# CtrlBoxV2.net
KiCad netlist of a schematic drawn in Altium Designer
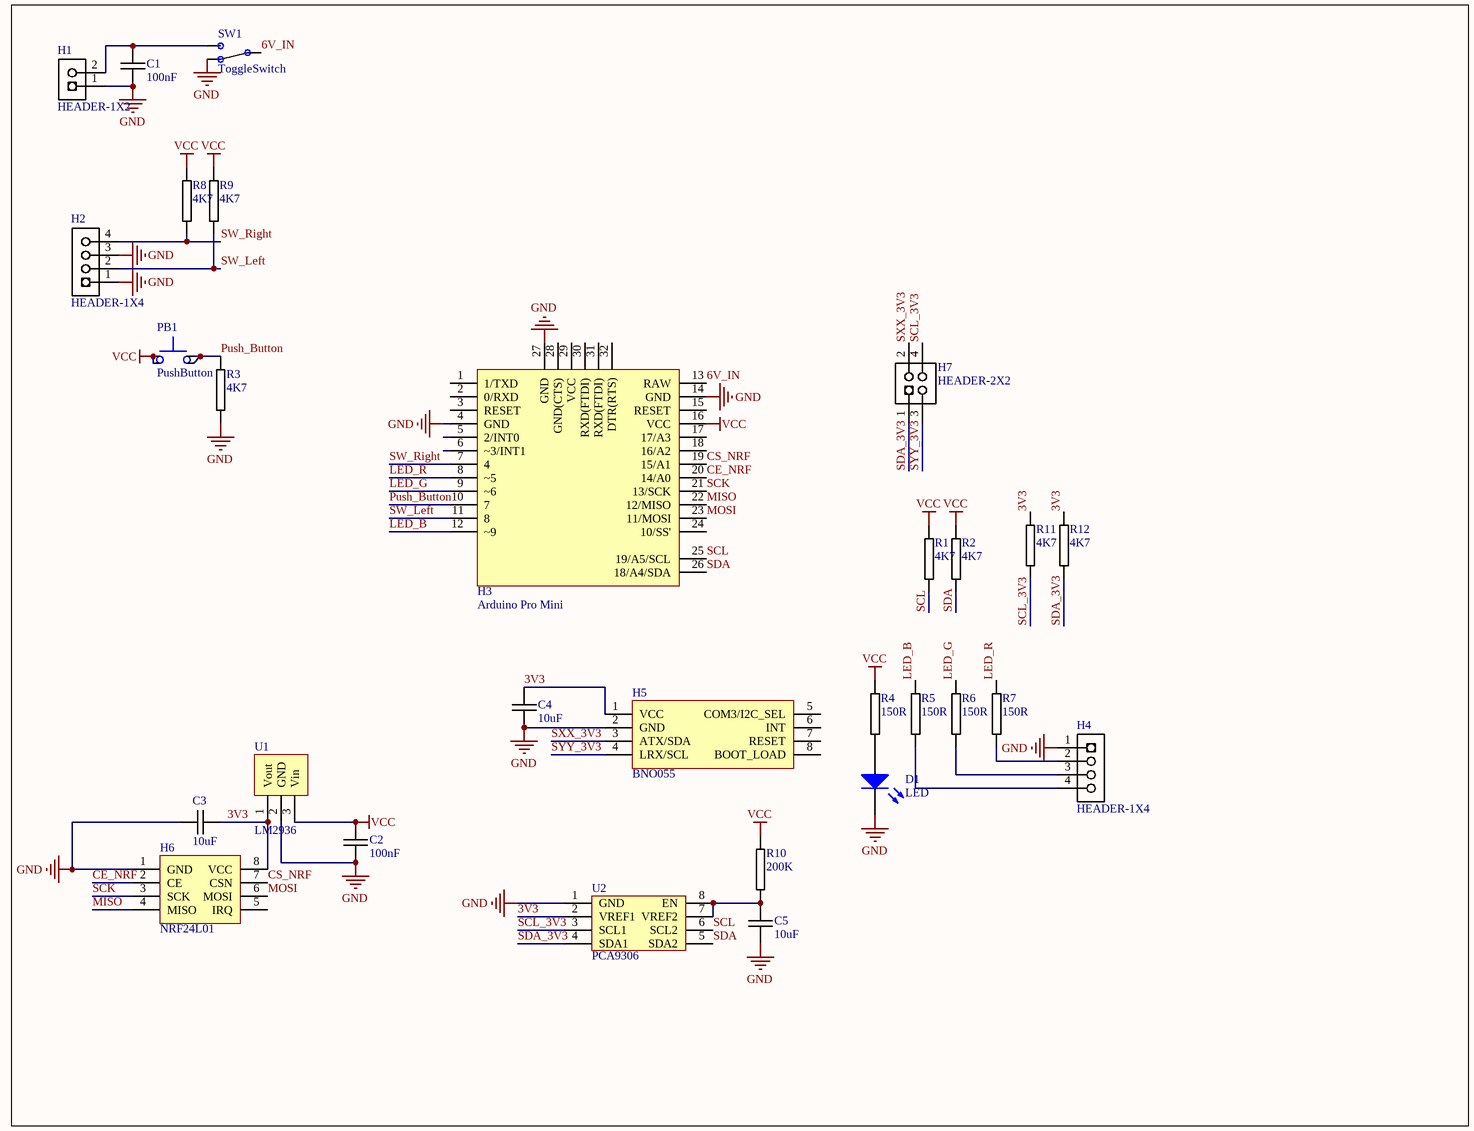
[diagram p0: CtrlBoxV2.SchDoc]

(export (version "E")
  (design (tool "Eeschema 10.0.6"))
  (components
    (comp (ref "C1")
      (value "100nF")
      (footprint "0805C-TBD")
      (description "CAPACITOR 0805 CERAMIC")
      (libsource (lib "vh_altium_library") (part "0805C-100nF-25V-X7R-MUR"))
    )
    (comp (ref "C2")
      (value "100nF")
      (footprint "0805C-TBD")
      (description "CAPACITOR 0805 CERAMIC")
      (libsource (lib "vh_altium_library") (part "0805C-100nF-25V-X7R-MUR"))
    )
    (comp (ref "C3")
      (value "10uF")
      (footprint "0805C-GENERIC")
      (description "CAPACITOR 0805 CERAMIC")
      (fields
        (field (name "MANUFACTURER PART NUMBER") "C2012X5R1C106M")
        (field (name "MANUFACTURER") "TDK Corporation")
      )
      (libsource (lib "vh_altium_library") (part "0805C-10UF-16V-X5R-TDK"))
    )
    (comp (ref "C4")
      (value "10uF")
      (footprint "0805C-GENERIC")
      (description "CAPACITOR 0805 CERAMIC")
      (fields
        (field (name "MANUFACTURER PART NUMBER") "C2012X5R1C106M")
        (field (name "MANUFACTURER") "TDK Corporation")
      )
      (libsource (lib "vh_altium_library") (part "0805C-10UF-16V-X5R-TDK"))
    )
    (comp (ref "C5")
      (value "10uF")
      (footprint "0805C-GENERIC")
      (description "CAPACITOR 0805 CERAMIC")
      (fields
        (field (name "MANUFACTURER PART NUMBER") "C2012X5R1C106M")
        (field (name "MANUFACTURER") "TDK Corporation")
      )
      (libsource (lib "vh_altium_library") (part "0805C-10UF-16V-X5R-TDK"))
    )
    (comp (ref "D1")
      (value "LED")
      (footprint "LED")
      (description "Small LED")
      (libsource (lib "Components") (part "LED"))
    )
    (comp (ref "H1")
      (value "HEADER-1X2")
      (footprint "HEADER-1X2")
      (libsource (lib "vh_altium_library") (part "HEADER-1X2"))
    )
    (comp (ref "H2")
      (value "HEADER-1X4")
      (footprint "HEADER-1X4")
      (libsource (lib "vh_altium_library") (part "HEADER-1X4"))
    )
    (comp (ref "H3")
      (value "Arduino Pro Mini")
      (footprint "Arduino Pro Mini")
      (libsource (lib "Components") (part "Arduino Pro Mini"))
    )
    (comp (ref "H4")
      (value "HEADER-1X4")
      (footprint "HEADER-1X4")
      (libsource (lib "vh_altium_library") (part "HEADER-1X4"))
    )
    (comp (ref "H5")
      (value "BNO055")
      (footprint "BNO055")
      (description "Accel+Gyro+Mag")
      (libsource (lib "Components") (part "BNO055"))
    )
    (comp (ref "H6")
      (value "NRF24L01")
      (footprint "NRF24L01")
      (description "Radio Transceiver")
      (libsource (lib "Components") (part "NRF24L01"))
    )
    (comp (ref "H7")
      (value "HEADER-2X2")
      (footprint "HEADER-2X2")
      (libsource (lib "vh_altium_library") (part "HEADER-2X2"))
    )
    (comp (ref "PB1")
      (value "PushButton")
      (footprint "PushButton")
      (libsource (lib "SBv1Components") (part "PushButton"))
    )
    (comp (ref "R1")
      (value "4K7")
      (footprint "0805R-4K7")
      (description "RESISTOR 0805 1/4 WATT THIN FILM")
      (libsource (lib "vh_altium_library") (part "0805R-4K7"))
    )
    (comp (ref "R2")
      (value "4K7")
      (footprint "0805R-4K7")
      (description "RESISTOR 0805 1/4 WATT THIN FILM")
      (libsource (lib "vh_altium_library") (part "0805R-4K7"))
    )
    (comp (ref "R3")
      (value "4K7")
      (footprint "0805R-4K7")
      (description "RESISTOR 0805 1/4 WATT THIN FILM")
      (libsource (lib "vh_altium_library") (part "0805R-4K7"))
    )
    (comp (ref "R4")
      (value "150R")
      (footprint "0805R-150")
      (description "RESISTOR 0805 1/4 WATT THIN FILM")
      (libsource (lib "vh_altium_library") (part "0805R-150"))
    )
    (comp (ref "R5")
      (value "150R")
      (footprint "0805R-150")
      (description "RESISTOR 0805 1/4 WATT THIN FILM")
      (libsource (lib "vh_altium_library") (part "0805R-150"))
    )
    (comp (ref "R6")
      (value "150R")
      (footprint "0805R-150")
      (description "RESISTOR 0805 1/4 WATT THIN FILM")
      (libsource (lib "vh_altium_library") (part "0805R-150"))
    )
    (comp (ref "R7")
      (value "150R")
      (footprint "0805R-150")
      (description "RESISTOR 0805 1/4 WATT THIN FILM")
      (libsource (lib "vh_altium_library") (part "0805R-150"))
    )
    (comp (ref "R8")
      (value "4K7")
      (footprint "0805R-4K7")
      (description "RESISTOR 0805 1/4 WATT THIN FILM")
      (libsource (lib "vh_altium_library") (part "0805R-4K7"))
    )
    (comp (ref "R9")
      (value "4K7")
      (footprint "0805R-4K7")
      (description "RESISTOR 0805 1/4 WATT THIN FILM")
      (libsource (lib "vh_altium_library") (part "0805R-4K7"))
    )
    (comp (ref "R10")
      (value "200K")
      (footprint "0805R-4K7")
      (description "RESISTOR 0805 1/4 WATT THIN FILM")
      (libsource (lib "vh_altium_library") (part "0805R-4K7"))
    )
    (comp (ref "R11")
      (value "4K7")
      (footprint "0805R-4K7")
      (description "RESISTOR 0805 1/4 WATT THIN FILM")
      (libsource (lib "vh_altium_library") (part "0805R-4K7"))
    )
    (comp (ref "R12")
      (value "4K7")
      (footprint "0805R-4K7")
      (description "RESISTOR 0805 1/4 WATT THIN FILM")
      (libsource (lib "vh_altium_library") (part "0805R-4K7"))
    )
    (comp (ref "SW1")
      (value "ToggleSwitch")
      (footprint "SWITCHFOOTPRINT")
      (libsource (lib "SBv1Components") (part "ToggleSwitch"))
    )
    (comp (ref "U1")
      (value "LM2936")
      (footprint "LM2936")
      (description "3V3 Voltage Regulator")
      (libsource (lib "Components") (part "LM2936"))
    )
    (comp (ref "U2")
      (value "PCA9306")
      (footprint "PCA9306")
      (description "Dual Bidirectional I2C Voltage Level Translator")
      (libsource (lib "Components") (part "PCA9306"))
    )
  )
  (nets
    (net (code "1") (name "/3V3") (class "Default")
      (node (ref "C3") (pin "2") (pintype "passive"))
      (node (ref "C4") (pin "1") (pintype "passive"))
      (node (ref "H5") (pin "1") (pinfunction "VCC_1") (pintype "passive"))
      (node (ref "H6") (pin "8") (pinfunction "VCC_8") (pintype "passive"))
      (node (ref "R11") (pin "1") (pintype "passive"))
      (node (ref "R12") (pin "1") (pintype "passive"))
      (node (ref "U1") (pin "1") (pinfunction "Vout_1") (pintype "passive"))
      (node (ref "U2") (pin "2") (pinfunction "VREF1_2") (pintype "passive"))
    )
    (net (code "2") (name "/6V_IN") (class "Default")
      (node (ref "H3") (pin "13") (pinfunction "RAW_13") (pintype "passive"))
      (node (ref "SW1") (pin "23") (pinfunction "23_23") (pintype "passive"))
    )
    (net (code "3") (name "/CE_NRF") (class "Default")
      (node (ref "H3") (pin "20") (pinfunction "14/A0_20") (pintype "passive"))
      (node (ref "H6") (pin "2") (pinfunction "CE_2") (pintype "passive"))
    )
    (net (code "4") (name "/CS_NRF") (class "Default")
      (node (ref "H3") (pin "19") (pinfunction "15/A1_19") (pintype "passive"))
      (node (ref "H6") (pin "7") (pinfunction "CSN_7") (pintype "passive"))
    )
    (net (code "5") (name "/LED_B") (class "Default")
      (node (ref "H3") (pin "12") (pinfunction "~9_12") (pintype "passive"))
      (node (ref "R5") (pin "1") (pintype "passive"))
    )
    (net (code "6") (name "/LED_G") (class "Default")
      (node (ref "H3") (pin "9") (pinfunction "~6_9") (pintype "passive"))
      (node (ref "R6") (pin "1") (pintype "passive"))
    )
    (net (code "7") (name "/LED_R") (class "Default")
      (node (ref "H3") (pin "8") (pinfunction "~5_8") (pintype "passive"))
      (node (ref "R7") (pin "1") (pintype "passive"))
    )
    (net (code "8") (name "/MISO") (class "Default")
      (node (ref "H3") (pin "22") (pinfunction "12/MISO_22") (pintype "passive"))
      (node (ref "H6") (pin "4") (pinfunction "MISO_4") (pintype "passive"))
    )
    (net (code "9") (name "/MOSI") (class "Default")
      (node (ref "H3") (pin "23") (pinfunction "11/MOSI_23") (pintype "passive"))
      (node (ref "H6") (pin "6") (pinfunction "MOSI_6") (pintype "passive"))
    )
    (net (code "10") (name "/Push_Button") (class "Default")
      (node (ref "H3") (pin "10") (pinfunction "7_10") (pintype "passive"))
      (node (ref "PB1") (pin "27") (pinfunction "27_27") (pintype "passive"))
      (node (ref "PB1") (pin "29") (pinfunction "29_29") (pintype "passive"))
      (node (ref "R3") (pin "1") (pintype "passive"))
    )
    (net (code "11") (name "/SCK") (class "Default")
      (node (ref "H3") (pin "21") (pinfunction "13/SCK_21") (pintype "passive"))
      (node (ref "H6") (pin "3") (pinfunction "SCK_3") (pintype "passive"))
    )
    (net (code "12") (name "/SCL") (class "Default")
      (node (ref "H3") (pin "25") (pinfunction "19/A5/SCL_25") (pintype "passive"))
      (node (ref "R1") (pin "2") (pintype "passive"))
      (node (ref "U2") (pin "6") (pinfunction "SCL2_6") (pintype "passive"))
    )
    (net (code "13") (name "/SCL_3V3") (class "Default")
      (node (ref "H7") (pin "4") (pintype "passive"))
      (node (ref "R11") (pin "2") (pintype "passive"))
      (node (ref "U2") (pin "3") (pinfunction "SCL1_3") (pintype "passive"))
    )
    (net (code "14") (name "/SDA") (class "Default")
      (node (ref "H3") (pin "26") (pinfunction "18/A4/SDA_26") (pintype "passive"))
      (node (ref "R2") (pin "2") (pintype "passive"))
      (node (ref "U2") (pin "5") (pinfunction "SDA2_5") (pintype "passive"))
    )
    (net (code "15") (name "/SDA_3V3") (class "Default")
      (node (ref "H7") (pin "1") (pintype "passive"))
      (node (ref "R12") (pin "2") (pintype "passive"))
      (node (ref "U2") (pin "4") (pinfunction "SDA1_4") (pintype "passive"))
    )
    (net (code "16") (name "/SW_Left") (class "Default")
      (node (ref "H2") (pin "2") (pintype "passive"))
      (node (ref "H3") (pin "11") (pinfunction "8_11") (pintype "passive"))
      (node (ref "R9") (pin "2") (pintype "passive"))
    )
    (net (code "17") (name "/SW_Right") (class "Default")
      (node (ref "H2") (pin "4") (pintype "passive"))
      (node (ref "H3") (pin "7") (pinfunction "4_7") (pintype "passive"))
      (node (ref "R8") (pin "2") (pintype "passive"))
    )
    (net (code "18") (name "/SXX_3V3") (class "Default")
      (node (ref "H5") (pin "3") (pinfunction "ATX/SDA_3") (pintype "passive"))
      (node (ref "H7") (pin "2") (pintype "passive"))
    )
    (net (code "19") (name "/SYY_3V3") (class "Default")
      (node (ref "H5") (pin "4") (pinfunction "LRX/SCL_4") (pintype "passive"))
      (node (ref "H7") (pin "3") (pintype "passive"))
    )
    (net (code "20") (name "GND") (class "Default")
      (node (ref "C1") (pin "1") (pintype "passive"))
      (node (ref "C2") (pin "2") (pintype "passive"))
      (node (ref "C3") (pin "1") (pintype "passive"))
      (node (ref "C4") (pin "2") (pintype "passive"))
      (node (ref "C5") (pin "2") (pintype "passive"))
      (node (ref "D1") (pin "2") (pinfunction "K_2") (pintype "passive"))
      (node (ref "H1") (pin "1") (pintype "passive"))
      (node (ref "H2") (pin "1") (pintype "passive"))
      (node (ref "H2") (pin "3") (pintype "passive"))
      (node (ref "H3") (pin "14") (pinfunction "GND_14") (pintype "passive"))
      (node (ref "H3") (pin "27") (pinfunction "GND_27") (pintype "passive"))
      (node (ref "H3") (pin "4") (pinfunction "GND_4") (pintype "passive"))
      (node (ref "H4") (pin "1") (pintype "passive"))
      (node (ref "H5") (pin "2") (pinfunction "GND_2") (pintype "passive"))
      (node (ref "H6") (pin "1") (pinfunction "GND_1") (pintype "passive"))
      (node (ref "R3") (pin "2") (pintype "passive"))
      (node (ref "SW1") (pin "24") (pinfunction "24_24") (pintype "passive"))
      (node (ref "U1") (pin "2") (pinfunction "GND_2") (pintype "passive"))
      (node (ref "U2") (pin "1") (pinfunction "GND_1") (pintype "passive"))
    )
    (net (code "21") (name "Net-(C1-Pad2)") (class "Default")
      (node (ref "C1") (pin "2") (pintype "passive"))
      (node (ref "H1") (pin "2") (pintype "passive"))
      (node (ref "SW1") (pin "25") (pinfunction "25_25") (pintype "passive"))
    )
    (net (code "22") (name "Net-(D1-A)") (class "Default")
      (node (ref "D1") (pin "1") (pinfunction "A_1") (pintype "passive"))
      (node (ref "R4") (pin "2") (pintype "passive"))
    )
    (net (code "23") (name "Net-(H4-Pad2)") (class "Default")
      (node (ref "H4") (pin "2") (pintype "passive"))
      (node (ref "R7") (pin "2") (pintype "passive"))
    )
    (net (code "24") (name "Net-(H4-Pad3)") (class "Default")
      (node (ref "H4") (pin "3") (pintype "passive"))
      (node (ref "R6") (pin "2") (pintype "passive"))
    )
    (net (code "25") (name "Net-(H4-Pad4)") (class "Default")
      (node (ref "H4") (pin "4") (pintype "passive"))
      (node (ref "R5") (pin "2") (pintype "passive"))
    )
    (net (code "26") (name "Net-(U2-EN)") (class "Default")
      (node (ref "C5") (pin "1") (pintype "passive"))
      (node (ref "R10") (pin "1") (pintype "passive"))
      (node (ref "U2") (pin "7") (pinfunction "VREF2_7") (pintype "passive"))
      (node (ref "U2") (pin "8") (pinfunction "EN_8") (pintype "passive"))
    )
    (net (code "27") (name "VCC") (class "Default")
      (node (ref "C2") (pin "1") (pintype "passive"))
      (node (ref "H3") (pin "16") (pinfunction "VCC_16") (pintype "passive"))
      (node (ref "PB1") (pin "26") (pinfunction "26_26") (pintype "passive"))
      (node (ref "PB1") (pin "28") (pinfunction "28_28") (pintype "passive"))
      (node (ref "R1") (pin "1") (pintype "passive"))
      (node (ref "R10") (pin "2") (pintype "passive"))
      (node (ref "R2") (pin "1") (pintype "passive"))
      (node (ref "R4") (pin "1") (pintype "passive"))
      (node (ref "R8") (pin "1") (pintype "passive"))
      (node (ref "R9") (pin "1") (pintype "passive"))
      (node (ref "U1") (pin "3") (pinfunction "Vin_3") (pintype "passive"))
    )
    (net (code "28") (name "unconnected-(H3-0{slash}RXD-Pad2)") (class "Default")
      (node (ref "H3") (pin "2") (pinfunction "0/RXD_2") (pintype "passive"))
    )
    (net (code "29") (name "unconnected-(H3-1{slash}TXD-Pad1)") (class "Default")
      (node (ref "H3") (pin "1") (pinfunction "1/TXD_1") (pintype "passive"))
    )
    (net (code "30") (name "unconnected-(H3-2{slash}INT0-Pad5)") (class "Default")
      (node (ref "H3") (pin "5") (pinfunction "2/INT0_5") (pintype "passive"))
    )
    (net (code "31") (name "unconnected-(H3-10{slash}SS'-Pad24)") (class "Default")
      (node (ref "H3") (pin "24") (pinfunction "10/SS'_24") (pintype "passive"))
    )
    (net (code "32") (name "unconnected-(H3-16{slash}A2-Pad18)") (class "Default")
      (node (ref "H3") (pin "18") (pinfunction "16/A2_18") (pintype "passive"))
    )
    (net (code "33") (name "unconnected-(H3-17{slash}A3-Pad17)") (class "Default")
      (node (ref "H3") (pin "17") (pinfunction "17/A3_17") (pintype "passive"))
    )
    (net (code "34") (name "unconnected-(H3-DTR(RTS)-Pad32)") (class "Default")
      (node (ref "H3") (pin "32") (pinfunction "DTR(RTS)_32") (pintype "passive"))
    )
    (net (code "35") (name "unconnected-(H3-GND(CTS)-Pad28)") (class "Default")
      (node (ref "H3") (pin "28") (pinfunction "GND(CTS)_28") (pintype "passive"))
    )
    (net (code "36") (name "unconnected-(H3-RESET-Pad3)") (class "Default")
      (node (ref "H3") (pin "3") (pinfunction "RESET_3") (pintype "passive"))
    )
    (net (code "37") (name "unconnected-(H3-RESET-Pad15)") (class "Default")
      (node (ref "H3") (pin "15") (pinfunction "RESET_15") (pintype "passive"))
    )
    (net (code "38") (name "unconnected-(H3-RXD(FTDI)-Pad30)") (class "Default")
      (node (ref "H3") (pin "30") (pinfunction "RXD(FTDI)_30") (pintype "passive"))
    )
    (net (code "39") (name "unconnected-(H3-RXD(FTDI)-Pad31)") (class "Default")
      (node (ref "H3") (pin "31") (pinfunction "RXD(FTDI)_31") (pintype "passive"))
    )
    (net (code "40") (name "unconnected-(H3-VCC-Pad29)") (class "Default")
      (node (ref "H3") (pin "29") (pinfunction "VCC_29") (pintype "passive"))
    )
    (net (code "41") (name "unconnected-(H3-~3{slash}INT1-Pad6)") (class "Default")
      (node (ref "H3") (pin "6") (pinfunction "~3/INT1_6") (pintype "passive"))
    )
    (net (code "42") (name "unconnected-(H5-BOOT_LOAD-Pad8)") (class "Default")
      (node (ref "H5") (pin "8") (pinfunction "BOOT_LOAD_8") (pintype "passive"))
    )
    (net (code "43") (name "unconnected-(H5-COM3{slash}I2C_SEL-Pad5)") (class "Default")
      (node (ref "H5") (pin "5") (pinfunction "COM3/I2C_SEL_5") (pintype "passive"))
    )
    (net (code "44") (name "unconnected-(H5-INT-Pad6)") (class "Default")
      (node (ref "H5") (pin "6") (pinfunction "INT_6") (pintype "passive"))
    )
    (net (code "45") (name "unconnected-(H5-RESET-Pad7)") (class "Default")
      (node (ref "H5") (pin "7") (pinfunction "RESET_7") (pintype "passive"))
    )
    (net (code "46") (name "unconnected-(H6-IRQ-Pad5)") (class "Default")
      (node (ref "H6") (pin "5") (pinfunction "IRQ_5") (pintype "passive"))
    )
  )
)
